# Cover_Sheet.net
KiCad netlist of a schematic drawn in Altium Designer
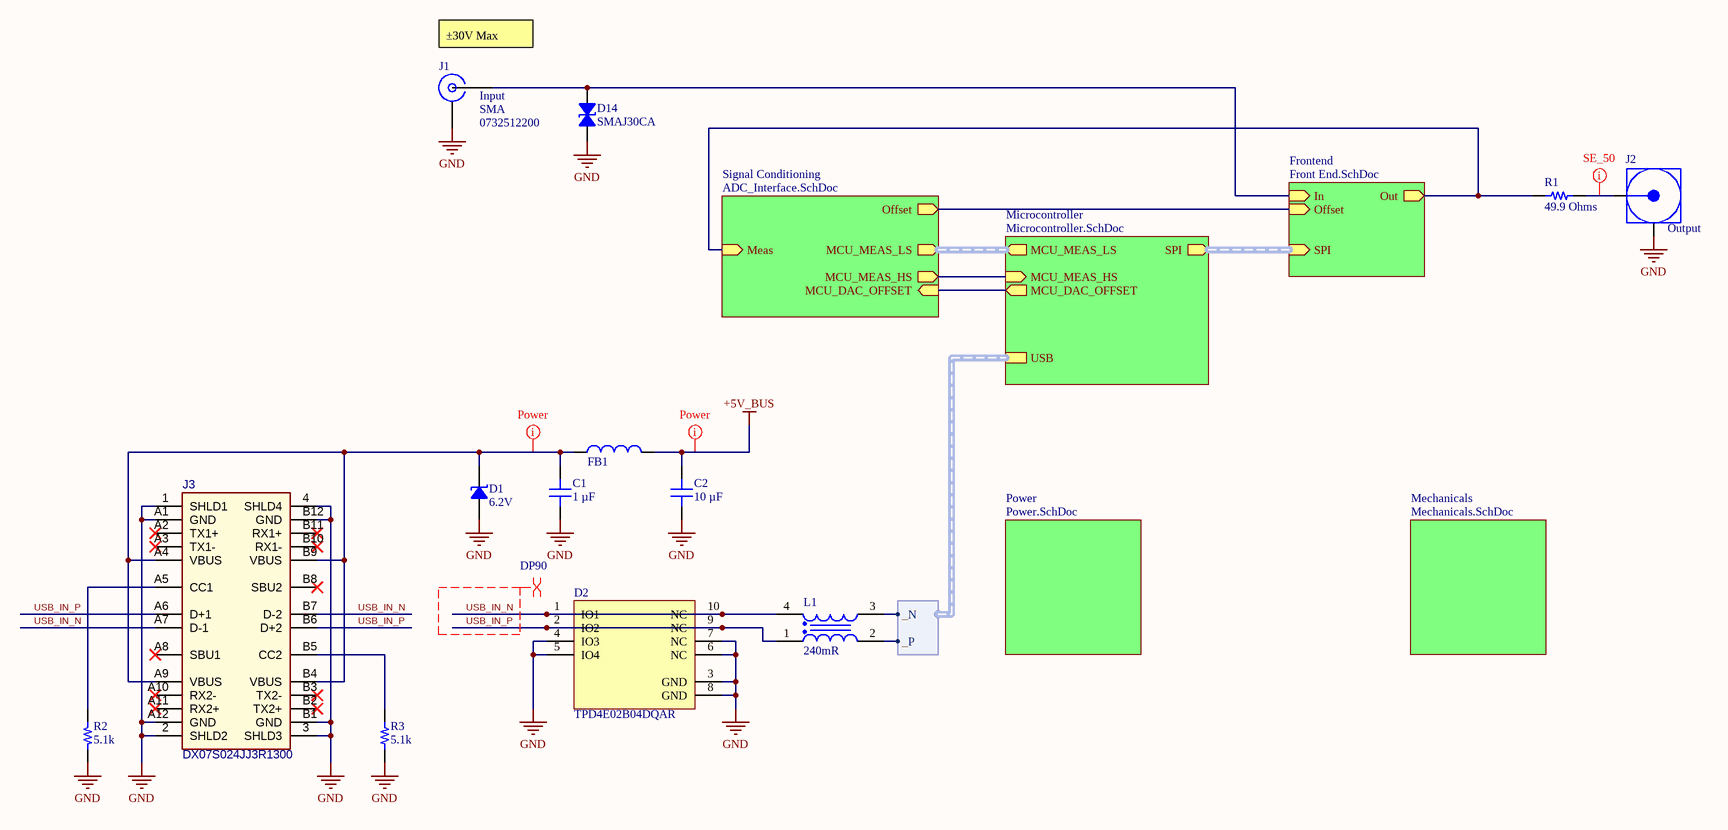
[diagram p0: Cover Sheet.SchDoc]

(export (version "E")
  (design (tool "Eeschema 10.0.6"))
  (components
    (comp (ref "C1")
      (value "1 µF")
      (footprint "CAP 0402_1005")
      (description "CAP CER 1UF 16V X5R 0402")
      (fields
        (field (name "PART NUMBER") "CL05A105KO5NNNC")
        (field (name "MANUFACTURER") "Samsung Electro-Mechanics")
      )
      (libsource (lib "Celestial Altium Library - altium_library") (part "Capacitor"))
    )
    (comp (ref "C2")
      (value "10 µF")
      (footprint "CAP 0805_2012")
      (description "CAP CER 10UF 25V X7S 0805")
      (fields
        (field (name "PART NUMBER") "GCM21BC71E106KE36L")
        (field (name "MANUFACTURER") "Murata Electronics")
      )
      (libsource (lib "Celestial Altium Library - altium_library") (part "Capacitor"))
    )
    (comp (ref "D1")
      (value "D5V0S1U2WS-7")
      (footprint "SOD323")
      (description "TVS DIODE 5.5V 16V SOD323")
      (fields
        (field (name "MANUFACTURER") "Diodes Incorporated")
        (field (name "VOLTAGE - BREAKDOWN (MIN)") "6.2V")
      )
      (libsource (lib "Celestial Altium Library - altium_library") (part "DIODE TVS UNI"))
    )
    (comp (ref "D2")
      (value "TPD4E02B04DQAR")
      (footprint "FP-DQA0010A-MFG")
      (description "Quad 0.25-pF, ±3.6-V, ±12-kV ESD protection diode for USB 3.0, HDMI 2.0 & High Speed Signals")
      (libsource (lib "Flycatcher Labs") (part "TPD4E02B04"))
    )
    (comp (ref "D14")
      (value "SMAJ30CA")
      (footprint "DO214AC SMA")
      (description "TVS DIODE 30VWM 48.4VC DO214AC")
      (fields (field (name "MANUFACTURER") "Littelfuse Inc."))
      (libsource (lib "Celestial Altium Library - altium_library") (part "Diode TVS"))
    )
    (comp (ref "FB1")
      (value "74279226101")
      (footprint "WE-MPSB_1812_L4.5W3.2H2.3")
      (description "Ferrite Beads Multi-Layer Power 100Ohm 25% 100MHz 8A 0.006Ohm DCR 1812 Automotive T/R")
      (fields (field (name "TOLERANCE") "25%"))
      (libsource (lib "Flycatcher Labs") (part "Ferrite"))
    )
    (comp (ref "J1")
      (value "Input")
      (footprint "MOLEX SD-73251-220 (NICKEL, 2.79MM FEET)")
      (description "CONN SMA JACK R/A 50 OHM PCB")
      (fields
        (field (name "CONNECTOR STYLE") "SMA")
        (field (name "PART NUMBER") "0732512200")
        (field (name "MANUFACTURER") "Molex")
      )
      (libsource (lib "Celestial Altium Library - altium_library") (part "COAXIAL JACK"))
    )
    (comp (ref "J2")
      (value "Output")
      (footprint "TE - 5227161-3")
      (description "RF BNC Connector, 1 Contact(s), Female, Panel Mount, Solder Terminal, Locking, Jack")
      (libsource (lib "Flycatcher Labs") (part "Connector-Coax"))
    )
    (comp (ref "J3")
      (value "DX07S024JJ3R1300")
      (footprint "JAE-DX07S024JJ3_V")
      (description "USB-C Connector, 20 V, 1.25 A, -30 to 80 degC, RoHS, Tape and Reel")
      (libsource (lib "Flycatcher Labs") (part "CMP-00171-5"))
    )
    (comp (ref "L1")
      (value "240mR")
      (footprint "WE-CNSW HF_0805")
      (description "WE-CNSW HF SMT Common Mode Line Filter (High Frequ")
      (fields (field (name "TOLERANCE") "25%") (field (name "Comment") "744233670"))
      (libsource (lib "Flycatcher Labs") (part "WE-CNSW"))
    )
    (comp (ref "R1")
      (value "49.9 Ohms")
      (footprint "RES 0805_2012")
      (description "RES SMD 49.9 OHM 1% 1/2W 0805")
      (fields (field (name "PART NUMBER") "CRCW080549R9FKEAHP") (field (name "MANUFACTURER") "Vishay Dale"))
      (libsource (lib "Celestial Altium Library - altium_library") (part "Resistor"))
    )
    (comp (ref "R2")
      (value "5.1k")
      (footprint "RES 0402_1005")
      (description "RES 5.1K OHM 1% 1/16W 0402")
      (fields (field (name "PART NUMBER") "CRCW04025K10FKEDC") (field (name "MANUFACTURER") "Vishay Dale"))
      (libsource (lib "Celestial Altium Library - altium_library") (part "Resistor"))
    )
    (comp (ref "R3")
      (value "5.1k")
      (footprint "RES 0402_1005")
      (description "RES 5.1K OHM 1% 1/16W 0402")
      (fields (field (name "PART NUMBER") "CRCW04025K10FKEDC") (field (name "MANUFACTURER") "Vishay Dale"))
      (libsource (lib "Celestial Altium Library - altium_library") (part "Resistor"))
    )
  )
  (nets
    (net (code "2") (name "+5V_BUS") (class "Default")
      (node (ref "C2") (pin "2") (pinfunction "2_2") (pintype "passive"))
      (node (ref "FB1") (pin "1") (pinfunction "1_1") (pintype "passive"))
    )
    (net (code "3") (name "/In") (class "Default")
      (node (ref "D14") (pin "2") (pinfunction "2_2") (pintype "passive"))
      (node (ref "J1") (pin "S") (pinfunction "SIGNAL_S") (pintype "passive"))
    )
    (net (code "8") (name "/Out") (class "Default")
      (node (ref "R1") (pin "1") (pinfunction "1_1") (pintype "passive"))
    )
    (net (code "10") (name "/USB_IN_N") (class "Default")
      (node (ref "D2") (pin "1") (pinfunction "IO1_1") (pintype "passive"))
      (node (ref "D2") (pin "10") (pinfunction "NC_10") (pintype "passive"))
      (node (ref "J3") (pin "A7") (pinfunction "D-1_A7") (pintype "passive"))
      (node (ref "J3") (pin "B7") (pinfunction "D-2_B7") (pintype "passive"))
      (node (ref "L1") (pin "4") (pinfunction "4_4") (pintype "passive"))
    )
    (net (code "11") (name "/USB_IN_P") (class "Default")
      (node (ref "D2") (pin "2") (pinfunction "IO2_2") (pintype "passive"))
      (node (ref "D2") (pin "9") (pinfunction "NC_9") (pintype "passive"))
      (node (ref "J3") (pin "A6") (pinfunction "D+1_A6") (pintype "passive"))
      (node (ref "J3") (pin "B6") (pinfunction "D+2_B6") (pintype "passive"))
      (node (ref "L1") (pin "1") (pinfunction "1_1") (pintype "passive"))
    )
    (net (code "12") (name "/_N") (class "Default")
      (node (ref "L1") (pin "3") (pinfunction "3_3") (pintype "passive"))
    )
    (net (code "13") (name "/_P") (class "Default")
      (node (ref "L1") (pin "2") (pinfunction "2_2") (pintype "passive"))
    )
    (net (code "15") (name "GND") (class "Default")
      (node (ref "C1") (pin "1") (pinfunction "1_1") (pintype "passive"))
      (node (ref "C2") (pin "1") (pinfunction "1_1") (pintype "passive"))
      (node (ref "D1") (pin "1") (pinfunction "1_1") (pintype "passive"))
      (node (ref "D14") (pin "1") (pinfunction "1_1") (pintype "passive"))
      (node (ref "D2") (pin "3") (pinfunction "GND_3") (pintype "power_in"))
      (node (ref "D2") (pin "4") (pinfunction "IO3_4") (pintype "passive"))
      (node (ref "D2") (pin "5") (pinfunction "IO4_5") (pintype "passive"))
      (node (ref "D2") (pin "6") (pinfunction "NC_6") (pintype "passive"))
      (node (ref "D2") (pin "7") (pinfunction "NC_7") (pintype "passive"))
      (node (ref "D2") (pin "8") (pinfunction "GND_8") (pintype "power_in"))
      (node (ref "J1") (pin "G") (pinfunction "GND_G") (pintype "passive"))
      (node (ref "J2") (pin "G") (pinfunction "GND_G") (pintype "passive"))
      (node (ref "J3") (pin "1") (pinfunction "SHLD1_1") (pintype "passive"))
      (node (ref "J3") (pin "2") (pinfunction "SHLD2_2") (pintype "passive"))
      (node (ref "J3") (pin "3") (pinfunction "SHLD3_3") (pintype "passive"))
      (node (ref "J3") (pin "4") (pinfunction "SHLD4_4") (pintype "passive"))
      (node (ref "J3") (pin "A1") (pinfunction "GND_A1") (pintype "passive"))
      (node (ref "J3") (pin "A12") (pinfunction "GND_A12") (pintype "passive"))
      (node (ref "J3") (pin "B1") (pinfunction "GND_B1") (pintype "passive"))
      (node (ref "J3") (pin "B12") (pinfunction "GND_B12") (pintype "passive"))
      (node (ref "R2") (pin "1") (pinfunction "1_1") (pintype "passive"))
      (node (ref "R3") (pin "1") (pinfunction "1_1") (pintype "passive"))
    )
    (net (code "16") (name "Net-(C1-Pad2)") (class "Default")
      (node (ref "C1") (pin "2") (pinfunction "2_2") (pintype "passive"))
      (node (ref "D1") (pin "2") (pinfunction "2_2") (pintype "passive"))
      (node (ref "FB1") (pin "2") (pinfunction "2_2") (pintype "passive"))
      (node (ref "J3") (pin "A4") (pinfunction "VBUS_A4") (pintype "passive"))
      (node (ref "J3") (pin "A9") (pinfunction "VBUS_A9") (pintype "passive"))
      (node (ref "J3") (pin "B4") (pinfunction "VBUS_B4") (pintype "passive"))
      (node (ref "J3") (pin "B9") (pinfunction "VBUS_B9") (pintype "passive"))
    )
    (net (code "17") (name "Net-(J2-Signal)") (class "Default")
      (node (ref "J2") (pin "S") (pinfunction "Signal_S") (pintype "passive"))
      (node (ref "R1") (pin "2") (pinfunction "2_2") (pintype "passive"))
    )
    (net (code "18") (name "Net-(J3-CC1)") (class "Default")
      (node (ref "J3") (pin "A5") (pinfunction "CC1_A5") (pintype "passive"))
      (node (ref "R2") (pin "2") (pinfunction "2_2") (pintype "passive"))
    )
    (net (code "19") (name "Net-(J3-CC2)") (class "Default")
      (node (ref "J3") (pin "B5") (pinfunction "CC2_B5") (pintype "passive"))
      (node (ref "R3") (pin "2") (pinfunction "2_2") (pintype "passive"))
    )
    (net (code "20") (name "unconnected-(J3-RX1+-PadB11)") (class "Default")
      (node (ref "J3") (pin "B11") (pinfunction "RX1+_B11") (pintype "passive+no_connect"))
    )
    (net (code "21") (name "unconnected-(J3-RX1--PadB10)") (class "Default")
      (node (ref "J3") (pin "B10") (pinfunction "RX1-_B10") (pintype "passive+no_connect"))
    )
    (net (code "22") (name "unconnected-(J3-RX2+-PadA11)") (class "Default")
      (node (ref "J3") (pin "A11") (pinfunction "RX2+_A11") (pintype "passive+no_connect"))
    )
    (net (code "23") (name "unconnected-(J3-RX2--PadA10)") (class "Default")
      (node (ref "J3") (pin "A10") (pinfunction "RX2-_A10") (pintype "passive+no_connect"))
    )
    (net (code "24") (name "unconnected-(J3-SBU1-PadA8)") (class "Default")
      (node (ref "J3") (pin "A8") (pinfunction "SBU1_A8") (pintype "passive+no_connect"))
    )
    (net (code "25") (name "unconnected-(J3-SBU2-PadB8)") (class "Default")
      (node (ref "J3") (pin "B8") (pinfunction "SBU2_B8") (pintype "passive+no_connect"))
    )
    (net (code "26") (name "unconnected-(J3-TX1+-PadA2)") (class "Default")
      (node (ref "J3") (pin "A2") (pinfunction "TX1+_A2") (pintype "passive+no_connect"))
    )
    (net (code "27") (name "unconnected-(J3-TX1--PadA3)") (class "Default")
      (node (ref "J3") (pin "A3") (pinfunction "TX1-_A3") (pintype "passive+no_connect"))
    )
    (net (code "28") (name "unconnected-(J3-TX2+-PadB2)") (class "Default")
      (node (ref "J3") (pin "B2") (pinfunction "TX2+_B2") (pintype "passive+no_connect"))
    )
    (net (code "29") (name "unconnected-(J3-TX2--PadB3)") (class "Default")
      (node (ref "J3") (pin "B3") (pinfunction "TX2-_B3") (pintype "passive+no_connect"))
    )
  )
)
